# snc98_main_cpu.net
KiCad netlist of a schematic drawn in EAGLE
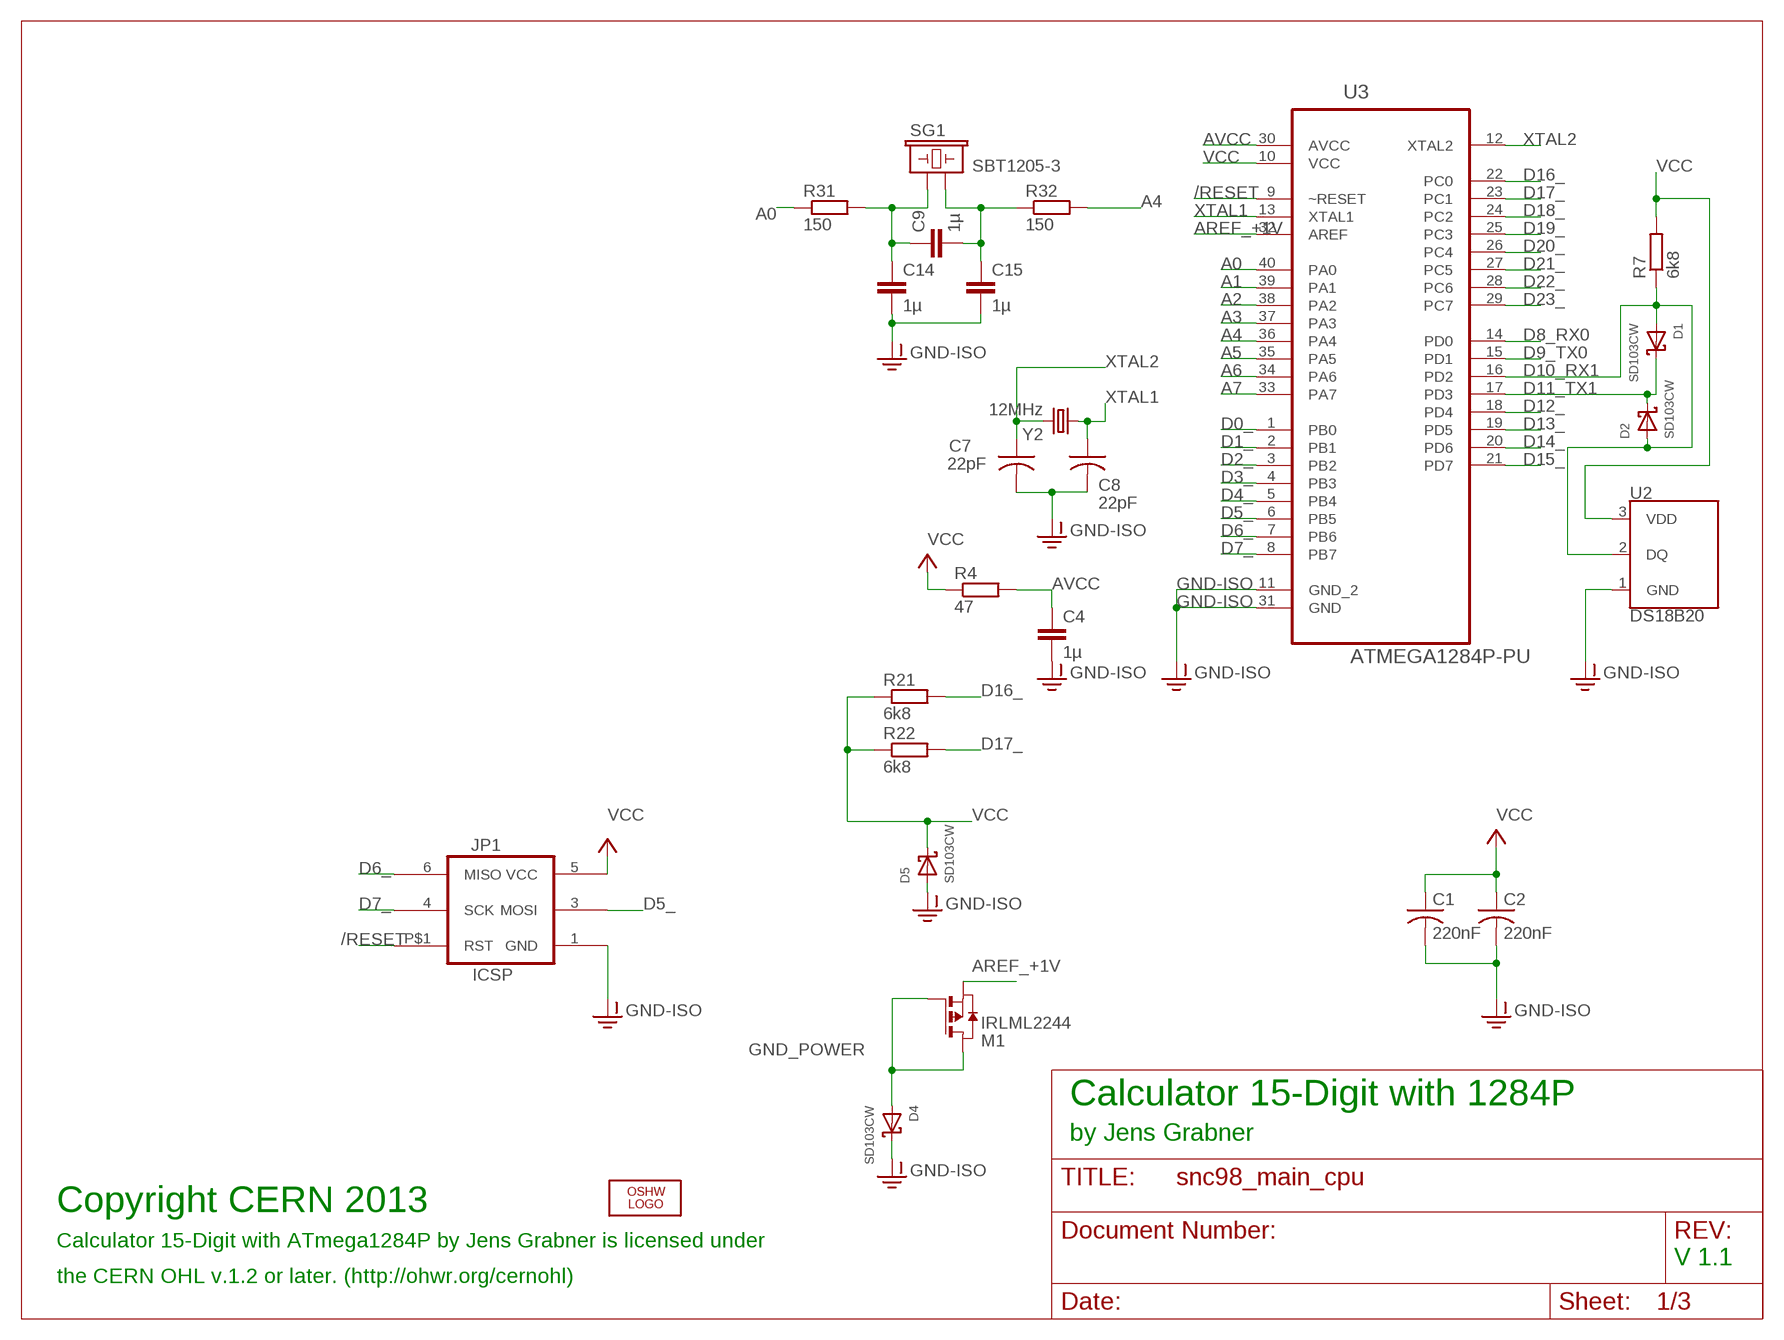
[diagram p0: schematic, sheet 1]
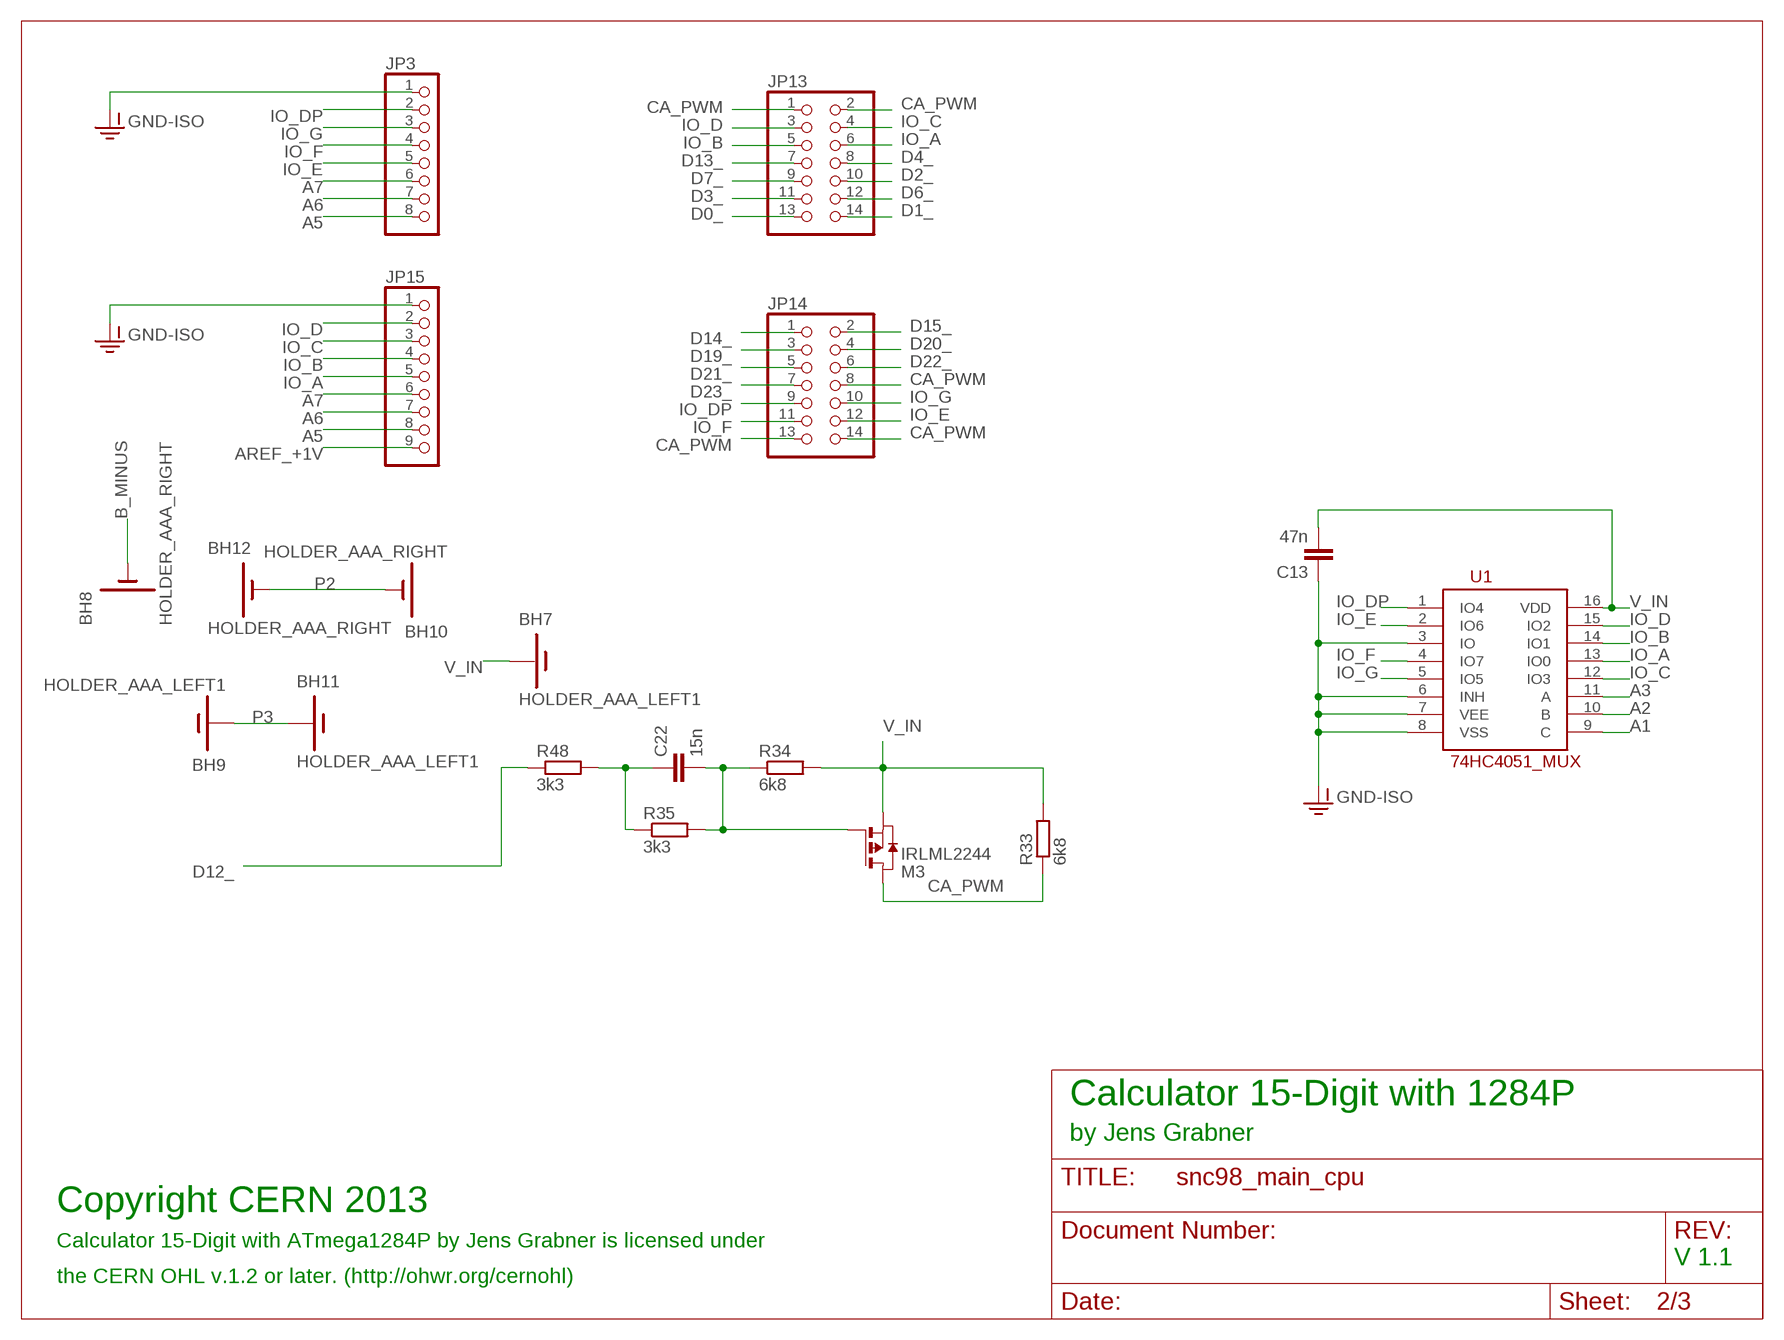
[diagram p1: schematic, sheet 2]
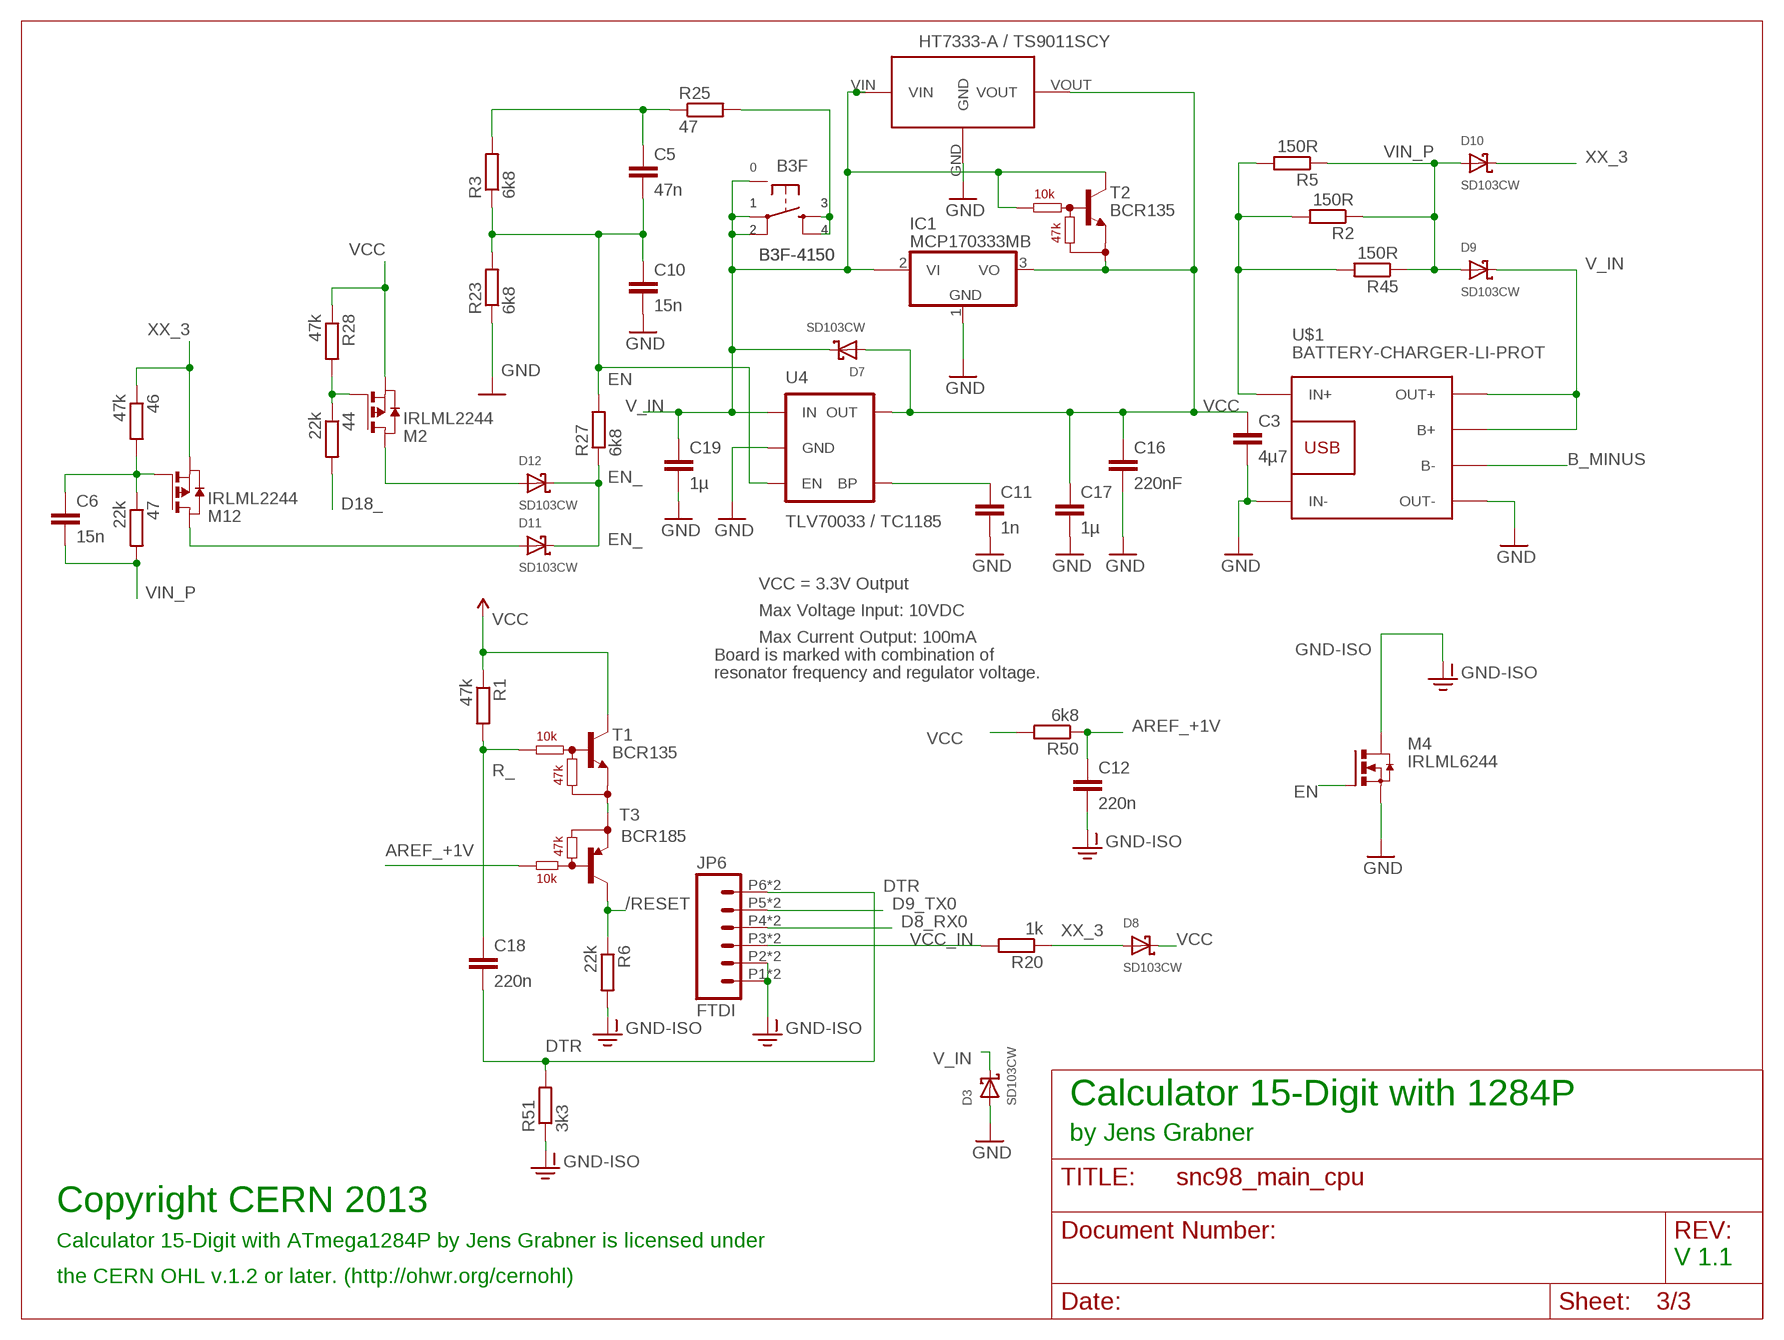
[diagram p2: schematic, sheet 3]

(export (version "E")
  (design (tool "Eeschema 10.0.6"))
  (components
    (comp (ref "BH7")
      (value "HOLDER_AAA_LEFT1")
      (footprint "eagle-import:BATTERY-AAA-LEFT")
      (libsource (lib "eagle-import") (part "HOLDER_AAA_LEFT1"))
    )
    (comp (ref "BH8")
      (value "HOLDER_AAA_RIGHT")
      (footprint "eagle-import:BATTERY-AAA-RIGHT")
      (libsource (lib "eagle-import") (part "HOLDER_AAA_RIGHT"))
    )
    (comp (ref "BH9")
      (value "HOLDER_AAA_LEFT1")
      (footprint "eagle-import:BATTERY-AAA-LEFT")
      (fields (field (name "TME_EU") "BC-0401"))
      (libsource (lib "eagle-import") (part "HOLDER_AAA_LEFT1"))
    )
    (comp (ref "BH10")
      (value "HOLDER_AAA_RIGHT")
      (footprint "eagle-import:BATTERY-AAA-RIGHT")
      (libsource (lib "eagle-import") (part "HOLDER_AAA_RIGHT"))
    )
    (comp (ref "BH11")
      (value "HOLDER_AAA_LEFT1")
      (footprint "eagle-import:BATTERY-AAA-LEFT")
      (libsource (lib "eagle-import") (part "HOLDER_AAA_LEFT1"))
    )
    (comp (ref "BH12")
      (value "HOLDER_AAA_RIGHT")
      (footprint "eagle-import:BATTERY-AAA-RIGHT")
      (libsource (lib "eagle-import") (part "HOLDER_AAA_RIGHT"))
    )
    (comp (ref "C13")
      (value "47n")
      (footprint "eagle-import:C1206K")
      (fields (field (name "TME_EU") "CC0805KRX7R9473"))
      (libsource (lib "eagle-import") (part "C-EUC1206K"))
    )
    (comp (ref "C22")
      (value "15n")
      (footprint "eagle-import:C1206K")
      (fields (field (name "TME_EU") "CC0805KRX7R9153"))
      (libsource (lib "eagle-import") (part "C-EUC1206K"))
    )
    (comp (ref "JP3")
      (value "PINHD-1X8CLEANBIG")
      (footprint "eagle-import:1X08-CLEANBIG")
      (libsource (lib "eagle-import") (part "PINHD-1X8CLEANBIG"))
    )
    (comp (ref "JP13")
      (value "PINHD-2X7")
      (footprint "eagle-import:2X07")
      (libsource (lib "eagle-import") (part "PINHD-2X7"))
    )
    (comp (ref "JP14")
      (value "PINHD-2X7")
      (footprint "eagle-import:2X07")
      (libsource (lib "eagle-import") (part "PINHD-2X7"))
    )
    (comp (ref "JP15")
      (value "PINHD-1X9")
      (footprint "eagle-import:1X09-BIG")
      (libsource (lib "eagle-import") (part "PINHD-1X9"))
    )
    (comp (ref "M3")
      (value "IRLML2244")
      (footprint "eagle-import:SOT-23")
      (fields (field (name "MF") "INFINEON") (field (name "MPN") "IRLML2244TRPBF"))
      (libsource (lib "eagle-import") (part "IRLML6402"))
    )
    (comp (ref "R33")
      (value "6k8")
      (footprint "eagle-import:R1206")
      (libsource (lib "eagle-import") (part "R-EU_R1206"))
    )
    (comp (ref "R34")
      (value "6k8")
      (footprint "eagle-import:R1206")
      (libsource (lib "eagle-import") (part "R-EU_R1206"))
    )
    (comp (ref "R35")
      (value "3k3")
      (footprint "eagle-import:R1206")
      (libsource (lib "eagle-import") (part "R-EU_R1206"))
    )
    (comp (ref "R48")
      (value "3k3")
      (footprint "eagle-import:R1206")
      (libsource (lib "eagle-import") (part "R-EU_R1206"))
    )
    (comp (ref "U1")
      (value "74HC4051_MUX")
      (footprint "eagle-import:SO16")
      (libsource (lib "eagle-import") (part "74HC4051_MUX"))
    )
    (comp (ref "44")
      (value "22k")
      (footprint "eagle-import:R1206")
      (libsource (lib "eagle-import") (part "R-EU_R1206"))
    )
    (comp (ref "46")
      (value "47k")
      (footprint "eagle-import:R1206")
      (libsource (lib "eagle-import") (part "R-EU_R1206"))
    )
    (comp (ref "47")
      (value "22k")
      (footprint "eagle-import:R1206")
      (libsource (lib "eagle-import") (part "R-EU_R1206"))
    )
    (comp (ref "C3")
      (value "4µ7")
      (footprint "eagle-import:C1206K")
      (libsource (lib "eagle-import") (part "C-EUC1206K"))
    )
    (comp (ref "C5")
      (value "47n")
      (footprint "eagle-import:C1206K")
      (fields (field (name "TME_EU") "CC0805KRX7R9473"))
      (libsource (lib "eagle-import") (part "C-EUC1206K"))
    )
    (comp (ref "C6")
      (value "15n")
      (footprint "eagle-import:C1206K")
      (fields (field (name "TME_EU") "CC0805KRX7R9153"))
      (libsource (lib "eagle-import") (part "C-EUC1206K"))
    )
    (comp (ref "C10")
      (value "15n")
      (footprint "eagle-import:C1206K")
      (fields (field (name "TME_EU") "CC0805KRX7R9153"))
      (libsource (lib "eagle-import") (part "C-EUC1206K"))
    )
    (comp (ref "C11")
      (value "1n")
      (footprint "eagle-import:0805")
      (libsource (lib "eagle-import") (part "CAP0805"))
    )
    (comp (ref "C12")
      (value "220n")
      (footprint "eagle-import:0805")
      (libsource (lib "eagle-import") (part "CAP0805"))
    )
    (comp (ref "C16")
      (value "220nF")
      (footprint "eagle-import:0805")
      (libsource (lib "eagle-import") (part "CAP0805"))
    )
    (comp (ref "C17")
      (value "1µ")
      (footprint "eagle-import:C1206K")
      (libsource (lib "eagle-import") (part "C-EUC1206K"))
    )
    (comp (ref "C18")
      (value "220n")
      (footprint "eagle-import:C1206K")
      (fields (field (name "TME_EU") "CC0805KPX7R7224"))
      (libsource (lib "eagle-import") (part "C-EUC1206K"))
    )
    (comp (ref "C19")
      (value "1µ")
      (footprint "eagle-import:C1206K")
      (libsource (lib "eagle-import") (part "C-EUC1206K"))
    )
    (comp (ref "D3")
      (value "SD103CW")
      (footprint "eagle-import:SOD-123F")
      (fields (field (name "MF") "MULTICOMP") (field (name "MPN") "SD103CW-7-F"))
      (libsource (lib "eagle-import") (part "DIODESOD-123F"))
    )
    (comp (ref "D7")
      (value "SD103CW")
      (footprint "eagle-import:SOD-123F")
      (fields (field (name "MF") "MULTICOMP") (field (name "MPN") "SD103CW-7-F"))
      (libsource (lib "eagle-import") (part "DIODESOD-123F"))
    )
    (comp (ref "D8")
      (value "SD103CW")
      (footprint "eagle-import:SOD-123F")
      (fields (field (name "MF") "MULTICOMP") (field (name "MPN") "SD103CW-7-F"))
      (libsource (lib "eagle-import") (part "DIODESOD-123F"))
    )
    (comp (ref "D9")
      (value "SD103CW")
      (footprint "eagle-import:SOD-123F")
      (fields (field (name "MF") "MULTICOMP") (field (name "MPN") "SD103CW-7-F"))
      (libsource (lib "eagle-import") (part "DIODESOD-123F"))
    )
    (comp (ref "D10")
      (value "SD103CW")
      (footprint "eagle-import:SOD-123F")
      (fields (field (name "MF") "MULTICOMP") (field (name "MPN") "SD103CW-7-F"))
      (libsource (lib "eagle-import") (part "DIODESOD-123F"))
    )
    (comp (ref "D11")
      (value "SD103CW")
      (footprint "eagle-import:SOD-123F")
      (fields (field (name "MF") "MULTICOMP") (field (name "MPN") "SD103CW-7-F"))
      (libsource (lib "eagle-import") (part "DIODESOD-123F"))
    )
    (comp (ref "D12")
      (value "SD103CW")
      (footprint "eagle-import:SOD-123F")
      (fields (field (name "MF") "MULTICOMP") (field (name "MPN") "SD103CW-7-F"))
      (libsource (lib "eagle-import") (part "DIODESOD-123F"))
    )
    (comp (ref "IC1")
      (value "MCP170333MB")
      (footprint "eagle-import:SOT89")
      (libsource (lib "eagle-import") (part "MCP1703MB33"))
    )
    (comp (ref "JP6")
      (value "FTDI")
      (footprint "eagle-import:1X06_LOCK")
      (libsource (lib "eagle-import") (part "M06LOCK"))
    )
    (comp (ref "M2")
      (value "IRLML2244")
      (footprint "eagle-import:SOT-23")
      (fields (field (name "MF") "INFINEON") (field (name "MPN") "IRLML2244TRPBF"))
      (libsource (lib "eagle-import") (part "IRLML6402"))
    )
    (comp (ref "M4")
      (value "IRLML6244")
      (footprint "eagle-import:SOT-23")
      (fields (field (name "MF") "INFINEON") (field (name "MPN") "IRLML6244TRPBF"))
      (libsource (lib "eagle-import") (part "IRLML2502M"))
    )
    (comp (ref "M12")
      (value "IRLML2244")
      (footprint "eagle-import:SOT-23")
      (fields (field (name "MF") "INFINEON") (field (name "MPN") "IRLML2244TRPBF"))
      (libsource (lib "eagle-import") (part "IRLML6402"))
    )
    (comp (ref "R1")
      (value "47k")
      (footprint "eagle-import:R1206")
      (libsource (lib "eagle-import") (part "R-EU_R1206"))
    )
    (comp (ref "R2")
      (value "150R")
      (footprint "eagle-import:0204_5")
      (libsource (lib "eagle-import") (part "R-EU_0204/5"))
    )
    (comp (ref "R3")
      (value "6k8")
      (footprint "eagle-import:R1206")
      (libsource (lib "eagle-import") (part "R-EU_R1206"))
    )
    (comp (ref "R5")
      (value "150R")
      (footprint "eagle-import:0207_10")
      (libsource (lib "eagle-import") (part "R-EU_0207/10"))
    )
    (comp (ref "R6")
      (value "22k")
      (footprint "eagle-import:R1206")
      (libsource (lib "eagle-import") (part "R-EU_R1206"))
    )
    (comp (ref "R20")
      (value "1k")
      (footprint "eagle-import:R1206")
      (libsource (lib "eagle-import") (part "R-EU_R1206"))
    )
    (comp (ref "R23")
      (value "6k8")
      (footprint "eagle-import:R1206")
      (libsource (lib "eagle-import") (part "R-EU_R1206"))
    )
    (comp (ref "R25")
      (value "47")
      (footprint "eagle-import:R1206")
      (libsource (lib "eagle-import") (part "R-EU_R1206"))
    )
    (comp (ref "R27")
      (value "6k8")
      (footprint "eagle-import:R1206")
      (libsource (lib "eagle-import") (part "R-EU_R1206"))
    )
    (comp (ref "R28")
      (value "47k")
      (footprint "eagle-import:R1206")
      (libsource (lib "eagle-import") (part "R-EU_R1206"))
    )
    (comp (ref "R45")
      (value "150R")
      (footprint "eagle-import:R1206")
      (libsource (lib "eagle-import") (part "R-EU_R1206"))
    )
    (comp (ref "R50")
      (value "6k8")
      (footprint "eagle-import:R1206")
      (libsource (lib "eagle-import") (part "R-EU_R1206"))
    )
    (comp (ref "R51")
      (value "3k3")
      (footprint "eagle-import:R1206")
      (libsource (lib "eagle-import") (part "R-EU_R1206"))
    )
    (comp (ref "S3")
      (value "B3F-4150")
      (footprint "eagle-import:TACTILE-PTH-12MM")
      (fields (field (name "MF") "OMRON") (field (name "MPN") "B3F4150"))
      (libsource (lib "eagle-import") (part "TACTILE_SWITCHTACTILE_SWITCH_PTH-12MM"))
    )
    (comp (ref "T1")
      (value "BCR135")
      (footprint "eagle-import:SOT23-BEC")
      (fields (field (name "MF") "INFINEON") (field (name "MPN") "BCR135E6327HTSA1"))
      (libsource (lib "eagle-import") (part "BCR135"))
    )
    (comp (ref "T2")
      (value "BCR135")
      (footprint "eagle-import:SOT23-BEC")
      (fields (field (name "MF") "INFINEON") (field (name "MPN") "BCR135E6327HTSA1"))
      (libsource (lib "eagle-import") (part "BCR135"))
    )
    (comp (ref "T3")
      (value "BCR185")
      (footprint "eagle-import:SOT23-R_INFINEON")
      (fields (field (name "MF") "ROHM") (field (name "MPN") "DTA114YKAT146"))
      (libsource (lib "eagle-import") (part "BCR185"))
    )
    (comp (ref "U$1")
      (value "BATTERY-CHARGER-LI-PROT")
      (footprint "eagle-import:BATTERY-CHARGER-LI-PROT")
      (libsource (lib "eagle-import") (part "BATTERY-CHARGER-LI-PROT"))
    )
    (comp (ref "U$3")
      (value "HT7333 / TS9011SCY")
      (footprint "eagle-import:SOT89")
      (libsource (lib "eagle-import") (part "HT7333"))
    )
    (comp (ref "U4")
      (value "TLV70033 / TC1185")
      (footprint "eagle-import:SOT23-5")
      (libsource (lib "eagle-import") (part "V_REG_LDOSMD"))
    )
    (comp (ref "C1")
      (value "220nF")
      (footprint "eagle-import:C1206K")
      (libsource (lib "eagle-import") (part "C-USC1206K"))
    )
    (comp (ref "C2")
      (value "220nF")
      (footprint "eagle-import:C1206K")
      (libsource (lib "eagle-import") (part "C-USC1206K"))
    )
    (comp (ref "C4")
      (value "1µ")
      (footprint "eagle-import:C1206K")
      (libsource (lib "eagle-import") (part "C-EUC1206K"))
    )
    (comp (ref "C7")
      (value "22pF")
      (footprint "eagle-import:C0805K")
      (libsource (lib "eagle-import") (part "C-USC0805K"))
    )
    (comp (ref "C8")
      (value "22pF")
      (footprint "eagle-import:C0805K")
      (libsource (lib "eagle-import") (part "C-USC0805K"))
    )
    (comp (ref "C9")
      (value "1µ")
      (footprint "eagle-import:C1206K")
      (libsource (lib "eagle-import") (part "C-EUC1206K"))
    )
    (comp (ref "C14")
      (value "1µ")
      (footprint "eagle-import:C1206K")
      (libsource (lib "eagle-import") (part "C-EUC1206K"))
    )
    (comp (ref "C15")
      (value "1µ")
      (footprint "eagle-import:C1206K")
      (libsource (lib "eagle-import") (part "C-EUC1206K"))
    )
    (comp (ref "D1")
      (value "SD103CW")
      (footprint "eagle-import:SOD-323")
      (fields (field (name "MF") "MULTICOMP") (field (name "MPN") "SD103CW-7-F"))
      (libsource (lib "eagle-import") (part "DIODESOD-323"))
    )
    (comp (ref "D2")
      (value "SD103CW")
      (footprint "eagle-import:SOD-123")
      (fields (field (name "MF") "MULTICOMP") (field (name "MPN") "SD103CW-7-F"))
      (libsource (lib "eagle-import") (part "DIODESOD-123"))
    )
    (comp (ref "D4")
      (value "SD103CW")
      (footprint "eagle-import:SOD-123F")
      (fields (field (name "MF") "MULTICOMP") (field (name "MPN") "SD103CW-7-F"))
      (libsource (lib "eagle-import") (part "DIODESOD-123F"))
    )
    (comp (ref "D5")
      (value "SD103CW")
      (footprint "eagle-import:SOD-123F")
      (fields (field (name "MF") "MULTICOMP") (field (name "MPN") "SD103CW-7-F"))
      (libsource (lib "eagle-import") (part "DIODESOD-123F"))
    )
    (comp (ref "JP1")
      (value "ICSP")
      (footprint "eagle-import:2X3_SMD_VERTICAL")
      (libsource (lib "eagle-import") (part "AVR_SPI_PRG_6"))
    )
    (comp (ref "LOGO1")
      (value "OSHW_LOGO_8MILX0150-NT")
      (footprint "eagle-import:OSHW_8X150_NOTEXT")
      (libsource (lib "eagle-import") (part "OSHW_LOGO_8MILX0150-NT"))
    )
    (comp (ref "M1")
      (value "IRLML2244")
      (footprint "eagle-import:SOT-23")
      (fields
        (field (name "MF") "INFINEON")
        (field (name "MPN") "IRLML2244TRPBF")
        (field (name "TME_EU") "DMG2305UX-7")
      )
      (libsource (lib "eagle-import") (part "IRLML6402"))
    )
    (comp (ref "R4")
      (value "47")
      (footprint "eagle-import:R1206")
      (libsource (lib "eagle-import") (part "R-EU_R1206"))
    )
    (comp (ref "R7")
      (value "6k8")
      (footprint "eagle-import:R1206")
      (libsource (lib "eagle-import") (part "R-EU_R1206"))
    )
    (comp (ref "R21")
      (value "6k8")
      (footprint "eagle-import:R1206")
      (libsource (lib "eagle-import") (part "R-EU_R1206"))
    )
    (comp (ref "R22")
      (value "6k8")
      (footprint "eagle-import:R1206")
      (libsource (lib "eagle-import") (part "R-EU_R1206"))
    )
    (comp (ref "R31")
      (value "150")
      (footprint "eagle-import:R1206")
      (libsource (lib "eagle-import") (part "R-EU_R1206"))
    )
    (comp (ref "R32")
      (value "150")
      (footprint "eagle-import:R1206")
      (libsource (lib "eagle-import") (part "R-EU_R1206"))
    )
    (comp (ref "SG1")
      (value "SBT1205-3")
      (footprint "eagle-import:BUZZER-12MM-NS")
      (libsource (lib "eagle-import") (part "BUZZERNS"))
    )
    (comp (ref "U2")
      (value "DS18B20")
      (footprint "eagle-import:TO-92-AMMO")
      (libsource (lib "eagle-import") (part "DS18B20"))
    )
    (comp (ref "U3")
      (value "ATMEGA1284P-PU")
      (footprint "eagle-import:DIP254P1524X483-40")
      (fields (field (name "MF") "MICROCHIP"))
      (libsource (lib "eagle-import") (part "ATMEGA1284P-PU"))
    )
    (comp (ref "Y2")
      (value "12MHz")
      (footprint "eagle-import:HC49U-V")
      (libsource (lib "eagle-import") (part "CRYSTALHC49UV"))
    )
  )
  (nets
    (net (code "1") (name "A0") (class "Default")
      (node (ref "R31") (pin "1") (pinfunction "1_1") (pintype "passive"))
      (node (ref "U3") (pin "40") (pinfunction "PA0_40") (pintype "bidirectional"))
    )
    (net (code "2") (name "A1") (class "Default")
      (node (ref "U1") (pin "9") (pinfunction "C_9") (pintype "bidirectional"))
      (node (ref "U3") (pin "39") (pinfunction "PA1_39") (pintype "bidirectional"))
    )
    (net (code "3") (name "A2") (class "Default")
      (node (ref "U1") (pin "10") (pinfunction "B_10") (pintype "bidirectional"))
      (node (ref "U3") (pin "38") (pinfunction "PA2_38") (pintype "bidirectional"))
    )
    (net (code "4") (name "A3") (class "Default")
      (node (ref "U1") (pin "11") (pinfunction "A_11") (pintype "bidirectional"))
      (node (ref "U3") (pin "37") (pinfunction "PA3_37") (pintype "bidirectional"))
    )
    (net (code "5") (name "A4") (class "Default")
      (node (ref "R32") (pin "2") (pinfunction "2_2") (pintype "passive"))
      (node (ref "U3") (pin "36") (pinfunction "PA4_36") (pintype "bidirectional"))
    )
    (net (code "6") (name "A5") (class "Default")
      (node (ref "JP15") (pin "8") (pinfunction "8_8") (pintype "passive"))
      (node (ref "JP3") (pin "8") (pinfunction "8_8") (pintype "passive"))
      (node (ref "U3") (pin "35") (pinfunction "PA5_35") (pintype "bidirectional"))
    )
    (net (code "7") (name "A6") (class "Default")
      (node (ref "JP15") (pin "7") (pinfunction "7_7") (pintype "passive"))
      (node (ref "JP3") (pin "7") (pinfunction "7_7") (pintype "passive"))
      (node (ref "U3") (pin "34") (pinfunction "PA6_34") (pintype "bidirectional"))
    )
    (net (code "8") (name "A7") (class "Default")
      (node (ref "JP15") (pin "6") (pinfunction "6_6") (pintype "passive"))
      (node (ref "JP3") (pin "6") (pinfunction "6_6") (pintype "passive"))
      (node (ref "U3") (pin "33") (pinfunction "PA7_33") (pintype "bidirectional"))
    )
    (net (code "9") (name "AREF_+1V") (class "Default")
      (node (ref "C12") (pin "3") (pinfunction "1_3") (pintype "passive"))
      (node (ref "JP15") (pin "9") (pinfunction "9_9") (pintype "passive"))
      (node (ref "M1") (pin "2") (pinfunction "S_2") (pintype "passive"))
      (node (ref "R50") (pin "1") (pinfunction "1_1") (pintype "passive"))
      (node (ref "T3") (pin "B") (pinfunction "B_B") (pintype "passive"))
      (node (ref "U3") (pin "32") (pinfunction "AREF_32") (pintype "input"))
    )
    (net (code "10") (name "AVCC") (class "Default")
      (node (ref "C4") (pin "1") (pinfunction "1_1") (pintype "passive"))
      (node (ref "R4") (pin "2") (pinfunction "2_2") (pintype "passive"))
      (node (ref "U3") (pin "30") (pinfunction "AVCC_30") (pintype "power_in"))
    )
    (net (code "11") (name "B_MINUS") (class "Default")
      (node (ref "BH8") (pin "M1") (pinfunction "-_M1") (pintype "power_in"))
      (node (ref "BH8") (pin "M2") (pinfunction "-_M2") (pintype "power_in"))
      (node (ref "BH8") (pin "M3") (pinfunction "-_M3") (pintype "power_in"))
      (node (ref "BH8") (pin "M4") (pinfunction "-_M4") (pintype "power_in"))
      (node (ref "U$1") (pin "B-") (pinfunction "B-_B-") (pintype "bidirectional"))
    )
    (net (code "12") (name "CA_PWM") (class "Default")
      (node (ref "JP13") (pin "1") (pinfunction "1_1") (pintype "passive"))
      (node (ref "JP13") (pin "2") (pinfunction "2_2") (pintype "passive"))
      (node (ref "JP14") (pin "13") (pinfunction "13_13") (pintype "passive"))
      (node (ref "JP14") (pin "14") (pinfunction "14_14") (pintype "passive"))
      (node (ref "JP14") (pin "8") (pinfunction "8_8") (pintype "passive"))
      (node (ref "M3") (pin "3") (pinfunction "D_3") (pintype "passive"))
      (node (ref "R33") (pin "1") (pinfunction "1_1") (pintype "passive"))
    )
    (net (code "13") (name "D0_") (class "Default")
      (node (ref "JP13") (pin "13") (pinfunction "13_13") (pintype "passive"))
      (node (ref "U3") (pin "1") (pinfunction "PB0_1") (pintype "bidirectional"))
    )
    (net (code "14") (name "D1_") (class "Default")
      (node (ref "JP13") (pin "14") (pinfunction "14_14") (pintype "passive"))
      (node (ref "U3") (pin "2") (pinfunction "PB1_2") (pintype "bidirectional"))
    )
    (net (code "15") (name "D2_") (class "Default")
      (node (ref "JP13") (pin "10") (pinfunction "10_10") (pintype "passive"))
      (node (ref "U3") (pin "3") (pinfunction "PB2_3") (pintype "bidirectional"))
    )
    (net (code "16") (name "D3_") (class "Default")
      (node (ref "JP13") (pin "11") (pinfunction "11_11") (pintype "passive"))
      (node (ref "U3") (pin "4") (pinfunction "PB3_4") (pintype "bidirectional"))
    )
    (net (code "17") (name "D4_") (class "Default")
      (node (ref "JP13") (pin "8") (pinfunction "8_8") (pintype "passive"))
      (node (ref "U3") (pin "5") (pinfunction "PB4_5") (pintype "bidirectional"))
    )
    (net (code "18") (name "D5_") (class "Default")
      (node (ref "JP1") (pin "3") (pinfunction "MOSI_3") (pintype "passive"))
      (node (ref "U3") (pin "6") (pinfunction "PB5_6") (pintype "bidirectional"))
    )
    (net (code "19") (name "D6_") (class "Default")
      (node (ref "JP1") (pin "6") (pinfunction "MISO_6") (pintype "passive"))
      (node (ref "JP13") (pin "12") (pinfunction "12_12") (pintype "passive"))
      (node (ref "U3") (pin "7") (pinfunction "PB6_7") (pintype "bidirectional"))
    )
    (net (code "20") (name "D7_") (class "Default")
      (node (ref "JP1") (pin "4") (pinfunction "SCK_4") (pintype "passive"))
      (node (ref "JP13") (pin "9") (pinfunction "9_9") (pintype "passive"))
      (node (ref "U3") (pin "8") (pinfunction "PB7_8") (pintype "bidirectional"))
    )
    (net (code "21") (name "D8_RX0") (class "Default")
      (node (ref "JP6") (pin "P4") (pinfunction "4_P4") (pintype "passive"))
      (node (ref "JP6") (pin "P4A") (pinfunction "4_P4A") (pintype "passive"))
      (node (ref "U3") (pin "14") (pinfunction "PD0_14") (pintype "bidirectional"))
    )
    (net (code "22") (name "D9_TX0") (class "Default")
      (node (ref "JP6") (pin "P5") (pinfunction "5_P5") (pintype "passive"))
      (node (ref "JP6") (pin "P5A") (pinfunction "5_P5A") (pintype "passive"))
      (node (ref "U3") (pin "15") (pinfunction "PD1_15") (pintype "bidirectional"))
    )
    (net (code "23") (name "D10_RX1") (class "Default")
      (node (ref "D1") (pin "A") (pinfunction "A_A") (pintype "passive"))
      (node (ref "D2") (pin "A") (pinfunction "A_A") (pintype "passive"))
      (node (ref "R7") (pin "1") (pinfunction "1_1") (pintype "passive"))
      (node (ref "U2") (pin "2") (pinfunction "DQ_2") (pintype "bidirectional"))
      (node (ref "U3") (pin "16") (pinfunction "PD2_16") (pintype "bidirectional"))
    )
    (net (code "24") (name "D11_TX1") (class "Default")
      (node (ref "D1") (pin "C") (pinfunction "C_C") (pintype "passive"))
      (node (ref "D2") (pin "C") (pinfunction "C_C") (pintype "passive"))
      (node (ref "U3") (pin "17") (pinfunction "PD3_17") (pintype "bidirectional"))
    )
    (net (code "25") (name "D12_") (class "Default")
      (node (ref "R48") (pin "1") (pinfunction "1_1") (pintype "passive"))
      (node (ref "U3") (pin "18") (pinfunction "PD4_18") (pintype "bidirectional"))
    )
    (net (code "26") (name "D13_") (class "Default")
      (node (ref "JP13") (pin "7") (pinfunction "7_7") (pintype "passive"))
      (node (ref "U3") (pin "19") (pinfunction "PD5_19") (pintype "bidirectional"))
    )
    (net (code "27") (name "D14_") (class "Default")
      (node (ref "JP14") (pin "1") (pinfunction "1_1") (pintype "passive"))
      (node (ref "U3") (pin "20") (pinfunction "PD6_20") (pintype "bidirectional"))
    )
    (net (code "28") (name "D15_") (class "Default")
      (node (ref "JP14") (pin "2") (pinfunction "2_2") (pintype "passive"))
      (node (ref "U3") (pin "21") (pinfunction "PD7_21") (pintype "bidirectional"))
    )
    (net (code "29") (name "D16_") (class "Default")
      (node (ref "R21") (pin "2") (pinfunction "2_2") (pintype "passive"))
      (node (ref "U3") (pin "22") (pinfunction "PC0_22") (pintype "bidirectional"))
    )
    (net (code "30") (name "D17_") (class "Default")
      (node (ref "R22") (pin "2") (pinfunction "2_2") (pintype "passive"))
      (node (ref "U3") (pin "23") (pinfunction "PC1_23") (pintype "bidirectional"))
    )
    (net (code "31") (name "D18_") (class "Default")
      (node (ref "44") (pin "2") (pinfunction "2_2") (pintype "passive"))
      (node (ref "U3") (pin "24") (pinfunction "PC2_24") (pintype "bidirectional"))
    )
    (net (code "32") (name "D19_") (class "Default")
      (node (ref "JP14") (pin "3") (pinfunction "3_3") (pintype "passive"))
      (node (ref "U3") (pin "25") (pinfunction "PC3_25") (pintype "bidirectional"))
    )
    (net (code "33") (name "D20_") (class "Default")
      (node (ref "JP14") (pin "4") (pinfunction "4_4") (pintype "passive"))
      (node (ref "U3") (pin "26") (pinfunction "PC4_26") (pintype "bidirectional"))
    )
    (net (code "34") (name "D21_") (class "Default")
      (node (ref "JP14") (pin "5") (pinfunction "5_5") (pintype "passive"))
      (node (ref "U3") (pin "27") (pinfunction "PC5_27") (pintype "bidirectional"))
    )
    (net (code "35") (name "D22_") (class "Default")
      (node (ref "JP14") (pin "6") (pinfunction "6_6") (pintype "passive"))
      (node (ref "U3") (pin "28") (pinfunction "PC6_28") (pintype "bidirectional"))
    )
    (net (code "36") (name "D23_") (class "Default")
      (node (ref "JP14") (pin "7") (pinfunction "7_7") (pintype "passive"))
      (node (ref "U3") (pin "29") (pinfunction "PC7_29") (pintype "bidirectional"))
    )
    (net (code "37") (name "DTR") (class "Default")
      (node (ref "C18") (pin "2") (pinfunction "2_2") (pintype "passive"))
      (node (ref "JP6") (pin "P6") (pinfunction "6_P6") (pintype "passive"))
      (node (ref "JP6") (pin "P6A") (pinfunction "6_P6A") (pintype "passive"))
      (node (ref "R51") (pin "2") (pinfunction "2_2") (pintype "passive"))
    )
    (net (code "38") (name "EN") (class "Default")
      (node (ref "C10") (pin "1") (pinfunction "1_1") (pintype "passive"))
      (node (ref "C5") (pin "2") (pinfunction "2_2") (pintype "passive"))
      (node (ref "M4") (pin "1") (pinfunction "G_1") (pintype "passive"))
      (node (ref "R23") (pin "2") (pinfunction "2_2") (pintype "passive"))
      (node (ref "R27") (pin "2") (pinfunction "2_2") (pintype "passive"))
      (node (ref "R3") (pin "1") (pinfunction "1_1") (pintype "passive"))
      (node (ref "U4") (pin "3") (pinfunction "EN_3") (pintype "input"))
    )
    (net (code "39") (name "EN_") (class "Default")
      (node (ref "D11") (pin "C") (pinfunction "C_C") (pintype "passive"))
      (node (ref "D12") (pin "C") (pinfunction "C_C") (pintype "passive"))
      (node (ref "R27") (pin "1") (pinfunction "1_1") (pintype "passive"))
    )
    (net (code "40") (name "GND") (class "Default")
      (node (ref "C10") (pin "2") (pinfunction "2_2") (pintype "passive"))
      (node (ref "C11") (pin "4") (pinfunction "2_4") (pintype "passive"))
      (node (ref "C16") (pin "4") (pinfunction "2_4") (pintype "passive"))
      (node (ref "C17") (pin "2") (pinfunction "2_2") (pintype "passive"))
      (node (ref "C19") (pin "2") (pinfunction "2_2") (pintype "passive"))
      (node (ref "C3") (pin "2") (pinfunction "2_2") (pintype "passive"))
      (node (ref "D3") (pin "A") (pinfunction "A_A") (pintype "passive"))
      (node (ref "IC1") (pin "1") (pinfunction "GND_1") (pintype "passive"))
      (node (ref "M4") (pin "2") (pinfunction "S_2") (pintype "passive"))
      (node (ref "R23") (pin "1") (pinfunction "1_1") (pintype "passive"))
      (node (ref "U$1") (pin "IN-") (pinfunction "IN-_IN-") (pintype "bidirectional"))
      (node (ref "U$1") (pin "OUT-") (pinfunction "OUT-_OUT-") (pintype "bidirectional"))
      (node (ref "U$3") (pin "GND") (pinfunction "GND_GND") (pintype "bidirectional"))
      (node (ref "U4") (pin "2") (pinfunction "GND_2") (pintype "input"))
    )
    (net (code "41") (name "GND-ISO") (class "Default")
      (node (ref "C1") (pin "2") (pinfunction "2_2") (pintype "passive"))
      (node (ref "C12") (pin "4") (pinfunction "2_4") (pintype "passive"))
      (node (ref "C13") (pin "1") (pinfunction "1_1") (pintype "passive"))
      (node (ref "C14") (pin "2") (pinfunction "2_2") (pintype "passive"))
      (node (ref "C15") (pin "2") (pinfunction "2_2") (pintype "passive"))
      (node (ref "C2") (pin "2") (pinfunction "2_2") (pintype "passive"))
      (node (ref "C4") (pin "2") (pinfunction "2_2") (pintype "passive"))
      (node (ref "C7") (pin "2") (pinfunction "2_2") (pintype "passive"))
      (node (ref "C8") (pin "2") (pinfunction "2_2") (pintype "passive"))
      (node (ref "D4") (pin "C") (pinfunction "C_C") (pintype "passive"))
      (node (ref "D5") (pin "A") (pinfunction "A_A") (pintype "passive"))
      (node (ref "JP1") (pin "1") (pinfunction "GND_1") (pintype "passive"))
      (node (ref "JP15") (pin "1") (pinfunction "1_1") (pintype "passive"))
      (node (ref "JP3") (pin "1") (pinfunction "1_1") (pintype "passive"))
      (node (ref "JP6") (pin "P1") (pinfunction "1_P1") (pintype "passive"))
      (node (ref "JP6") (pin "P1A") (pinfunction "1_P1A") (pintype "passive"))
      (node (ref "JP6") (pin "P2") (pinfunction "2_P2") (pintype "passive"))
      (node (ref "JP6") (pin "P2A") (pinfunction "2_P2A") (pintype "passive"))
      (node (ref "M4") (pin "3") (pinfunction "D_3") (pintype "passive"))
      (node (ref "R51") (pin "1") (pinfunction "1_1") (pintype "passive"))
      (node (ref "R6") (pin "2") (pinfunction "2_2") (pintype "passive"))
      (node (ref "U1") (pin "3") (pinfunction "IO_3") (pintype "bidirectional"))
      (node (ref "U1") (pin "6") (pinfunction "INH_6") (pintype "bidirectional"))
      (node (ref "U1") (pin "7") (pinfunction "VEE_7") (pintype "bidirectional"))
      (node (ref "U1") (pin "8") (pinfunction "VSS_8") (pintype "bidirectional"))
      (node (ref "U2") (pin "1") (pinfunction "GND_1") (pintype "power_in"))
      (node (ref "U3") (pin "11") (pinfunction "GND_2_11") (pintype "passive"))
      (node (ref "U3") (pin "31") (pinfunction "GND_31") (pintype "passive"))
    )
    (net (code "42") (name "GND_POWER") (class "Default")
      (node (ref "D4") (pin "A") (pinfunction "A_A") (pintype "passive"))
      (node (ref "M1") (pin "1") (pinfunction "G_1") (pintype "passive"))
      (node (ref "M1") (pin "3") (pinfunction "D_3") (pintype "passive"))
    )
    (net (code "43") (name "IO_A") (class "Default")
      (node (ref "JP13") (pin "6") (pinfunction "6_6") (pintype "passive"))
      (node (ref "JP15") (pin "5") (pinfunction "5_5") (pintype "passive"))
      (node (ref "U1") (pin "13") (pinfunction "IO0_13") (pintype "bidirectional"))
    )
    (net (code "44") (name "IO_B") (class "Default")
      (node (ref "JP13") (pin "5") (pinfunction "5_5") (pintype "passive"))
      (node (ref "JP15") (pin "4") (pinfunction "4_4") (pintype "passive"))
      (node (ref "U1") (pin "14") (pinfunction "IO1_14") (pintype "bidirectional"))
    )
    (net (code "45") (name "IO_C") (class "Default")
      (node (ref "JP13") (pin "4") (pinfunction "4_4") (pintype "passive"))
      (node (ref "JP15") (pin "3") (pinfunction "3_3") (pintype "passive"))
      (node (ref "U1") (pin "12") (pinfunction "IO3_12") (pintype "bidirectional"))
    )
    (net (code "46") (name "IO_D") (class "Default")
      (node (ref "JP13") (pin "3") (pinfunction "3_3") (pintype "passive"))
      (node (ref "JP15") (pin "2") (pinfunction "2_2") (pintype "passive"))
      (node (ref "U1") (pin "15") (pinfunction "IO2_15") (pintype "bidirectional"))
    )
    (net (code "47") (name "IO_DP") (class "Default")
      (node (ref "JP14") (pin "9") (pinfunction "9_9") (pintype "passive"))
      (node (ref "JP3") (pin "2") (pinfunction "2_2") (pintype "passive"))
      (node (ref "U1") (pin "1") (pinfunction "IO4_1") (pintype "bidirectional"))
    )
    (net (code "48") (name "IO_E") (class "Default")
      (node (ref "JP14") (pin "12") (pinfunction "12_12") (pintype "passive"))
      (node (ref "JP3") (pin "5") (pinfunction "5_5") (pintype "passive"))
      (node (ref "U1") (pin "2") (pinfunction "IO6_2") (pintype "bidirectional"))
    )
    (net (code "49") (name "IO_F") (class "Default")
      (node (ref "JP14") (pin "11") (pinfunction "11_11") (pintype "passive"))
      (node (ref "JP3") (pin "4") (pinfunction "4_4") (pintype "passive"))
      (node (ref "U1") (pin "4") (pinfunction "IO7_4") (pintype "bidirectional"))
    )
    (net (code "50") (name "IO_G") (class "Default")
      (node (ref "JP14") (pin "10") (pinfunction "10_10") (pintype "passive"))
      (node (ref "JP3") (pin "3") (pinfunction "3_3") (pintype "passive"))
      (node (ref "U1") (pin "5") (pinfunction "IO5_5") (pintype "bidirectional"))
    )
    (net (code "51") (name "Net-(C5-Pad1)") (class "Default")
      (node (ref "C5") (pin "1") (pinfunction "1_1") (pintype "passive"))
      (node (ref "R25") (pin "1") (pinfunction "1_1") (pintype "passive"))
      (node (ref "R3") (pin "2") (pinfunction "2_2") (pintype "passive"))
    )
    (net (code "52") (name "Net-(C11-1)") (class "Default")
      (node (ref "C11") (pin "3") (pinfunction "1_3") (pintype "passive"))
      (node (ref "U4") (pin "4") (pinfunction "BP_4") (pintype "input"))
    )
    (net (code "53") (name "Net-(C22-Pad1)") (class "Default")
      (node (ref "C22") (pin "1") (pinfunction "1_1") (pintype "passive"))
      (node (ref "R35") (pin "1") (pinfunction "1_1") (pintype "passive"))
      (node (ref "R48") (pin "2") (pinfunction "2_2") (pintype "passive"))
    )
    (net (code "54") (name "Net-(M2-D)") (class "Default")
      (node (ref "D12") (pin "A") (pinfunction "A_A") (pintype "passive"))
      (node (ref "M2") (pin "3") (pinfunction "D_3") (pintype "passive"))
    )
    (net (code "55") (name "Net-(M2-G)") (class "Default")
      (node (ref "44") (pin "1") (pinfunction "1_1") (pintype "passive"))
      (node (ref "M2") (pin "1") (pinfunction "G_1") (pintype "passive"))
      (node (ref "R28") (pin "2") (pinfunction "2_2") (pintype "passive"))
    )
    (net (code "56") (name "Net-(M3-G)") (class "Default")
      (node (ref "C22") (pin "2") (pinfunction "2_2") (pintype "passive"))
      (node (ref "M3") (pin "1") (pinfunction "G_1") (pintype "passive"))
      (node (ref "R34") (pin "1") (pinfunction "1_1") (pintype "passive"))
      (node (ref "R35") (pin "2") (pinfunction "2_2") (pintype "passive"))
    )
    (net (code "57") (name "Net-(M12-D)") (class "Default")
      (node (ref "D11") (pin "A") (pinfunction "A_A") (pintype "passive"))
      (node (ref "M12") (pin "3") (pinfunction "D_3") (pintype "passive"))
    )
    (net (code "58") (name "Net-(M12-G)") (class "Default")
      (node (ref "46") (pin "2") (pinfunction "2_2") (pintype "passive"))
      (node (ref "47") (pin "1") (pinfunction "1_1") (pintype "passive"))
      (node (ref "C6") (pin "1") (pinfunction "1_1") (pintype "passive"))
      (node (ref "M12") (pin "1") (pinfunction "G_1") (pintype "passive"))
    )
    (net (code "59") (name "Net-(R2-Pad2)") (class "Default")
      (node (ref "R2") (pin "2") (pinfunction "2_2") (pintype "passive"))
      (node (ref "R45") (pin "2") (pinfunction "2_2") (pintype "passive"))
      (node (ref "R5") (pin "2") (pinfunction "2_2") (pintype "passive"))
      (node (ref "U$1") (pin "IN+") (pinfunction "IN+_IN+") (pintype "bidirectional"))
    )
    (net (code "60") (name "Net-(R25-Pad2)") (class "Default")
      (node (ref "R25") (pin "2") (pinfunction "2_2") (pintype "passive"))
      (node (ref "S3") (pin "P$13") (pinfunction "3_P$13") (pintype "passive"))
      (node (ref "S3") (pin "P$14") (pinfunction "4_P$14") (pintype "passive"))
      (node (ref "S3") (pin "P$23") (pinfunction "3_P$23") (pintype "passive"))
      (node (ref "S3") (pin "P$24") (pinfunction "4_P$24") (pintype "passive"))
      (node (ref "S3") (pin "P$3") (pinfunction "3_P$3") (pintype "passive"))
      (node (ref "S3") (pin "P$4") (pinfunction "4_P$4") (pintype "passive"))
    )
    (net (code "61") (name "Net-(SG1-1)") (class "Default")
      (node (ref "C14") (pin "1") (pinfunction "1_1") (pintype "passive"))
      (node (ref "C9") (pin "1") (pinfunction "1_1") (pintype "passive"))
      (node (ref "R31") (pin "2") (pinfunction "2_2") (pintype "passive"))
      (node (ref "SG1") (pin "+") (pinfunction "1_+") (pintype "passive"))
    )
    (net (code "62") (name "Net-(SG1-2)") (class "Default")
      (node (ref "C15") (pin "1") (pinfunction "1_1") (pintype "passive"))
      (node (ref "C9") (pin "2") (pinfunction "2_2") (pintype "passive"))
      (node (ref "R32") (pin "1") (pinfunction "1_1") (pintype "passive"))
      (node (ref "SG1") (pin "-") (pinfunction "2_-") (pintype "passive"))
    )
    (net (code "63") (name "Net-(T1-PadE)") (class "Default")
      (node (ref "T1") (pin "E") (pinfunction "E_E") (pintype "passive"))
      (node (ref "T3") (pin "E") (pinfunction "E_E") (pintype "passive"))
    )
    (net (code "64") (name "P2") (class "Default")
      (node (ref "BH10") (pin "M1") (pinfunction "-_M1") (pintype "power_in"))
      (node (ref "BH10") (pin "M2") (pinfunction "-_M2") (pintype "power_in"))
      (node (ref "BH10") (pin "M3") (pinfunction "-_M3") (pintype "power_in"))
      (node (ref "BH10") (pin "M4") (pinfunction "-_M4") (pintype "power_in"))
      (node (ref "BH12") (pin "M1") (pinfunction "-_M1") (pintype "power_in"))
      (node (ref "BH12") (pin "M2") (pinfunction "-_M2") (pintype "power_in"))
      (node (ref "BH12") (pin "M3") (pinfunction "-_M3") (pintype "power_in"))
      (node (ref "BH12") (pin "M4") (pinfunction "-_M4") (pintype "power_in"))
    )
    (net (code "65") (name "P3") (class "Default")
      (node (ref "BH11") (pin "P1") (pinfunction "+_P1") (pintype "power_in"))
      (node (ref "BH11") (pin "P2") (pinfunction "+_P2") (pintype "power_in"))
      (node (ref "BH11") (pin "P3") (pinfunction "+_P3") (pintype "power_in"))
      (node (ref "BH11") (pin "P4") (pinfunction "+_P4") (pintype "power_in"))
      (node (ref "BH9") (pin "P1") (pinfunction "+_P1") (pintype "power_in"))
      (node (ref "BH9") (pin "P2") (pinfunction "+_P2") (pintype "power_in"))
      (node (ref "BH9") (pin "P3") (pinfunction "+_P3") (pintype "power_in"))
      (node (ref "BH9") (pin "P4") (pinfunction "+_P4") (pintype "power_in"))
    )
    (net (code "66") (name "R_") (class "Default")
      (node (ref "C18") (pin "1") (pinfunction "1_1") (pintype "passive"))
      (node (ref "R1") (pin "2") (pinfunction "2_2") (pintype "passive"))
      (node (ref "T1") (pin "B") (pinfunction "B_B") (pintype "passive"))
    )
    (net (code "67") (name "VCC") (class "Default")
      (node (ref "C1") (pin "1") (pinfunction "1_1") (pintype "passive"))
      (node (ref "C16") (pin "3") (pinfunction "1_3") (pintype "passive"))
      (node (ref "C17") (pin "1") (pinfunction "1_1") (pintype "passive"))
      (node (ref "C2") (pin "1") (pinfunction "1_1") (pintype "passive"))
      (node (ref "C3") (pin "1") (pinfunction "1_1") (pintype "passive"))
      (node (ref "D5") (pin "C") (pinfunction "C_C") (pintype "passive"))
      (node (ref "D7") (pin "A") (pinfunction "A_A") (pintype "passive"))
      (node (ref "D8") (pin "C") (pinfunction "C_C") (pintype "passive"))
      (node (ref "IC1") (pin "3") (pinfunction "VO_3") (pintype "passive"))
      (node (ref "JP1") (pin "5") (pinfunction "VCC_5") (pintype "passive"))
      (node (ref "M2") (pin "2") (pinfunction "S_2") (pintype "passive"))
      (node (ref "R1") (pin "1") (pinfunction "1_1") (pintype "passive"))
      (node (ref "R21") (pin "1") (pinfunction "1_1") (pintype "passive"))
      (node (ref "R22") (pin "1") (pinfunction "1_1") (pintype "passive"))
      (node (ref "R28") (pin "1") (pinfunction "1_1") (pintype "passive"))
      (node (ref "R4") (pin "1") (pinfunction "1_1") (pintype "passive"))
      (node (ref "R50") (pin "2") (pinfunction "2_2") (pintype "passive"))
      (node (ref "R7") (pin "2") (pinfunction "2_2") (pintype "passive"))
      (node (ref "T1") (pin "C") (pinfunction "C_C") (pintype "passive"))
      (node (ref "T2") (pin "E") (pinfunction "E_E") (pintype "passive"))
      (node (ref "U$3") (pin "VOUT") (pinfunction "VOUT_VOUT") (pintype "bidirectional"))
      (node (ref "U2") (pin "3") (pinfunction "VDD_3") (pintype "power_in"))
      (node (ref "U3") (pin "10") (pinfunction "VCC_10") (pintype "power_in"))
      (node (ref "U4") (pin "5") (pinfunction "OUT_5") (pintype "passive"))
    )
    (net (code "68") (name "VCC_IN") (class "Default")
      (node (ref "JP6") (pin "P3") (pinfunction "3_P3") (pintype "passive"))
      (node (ref "JP6") (pin "P3A") (pinfunction "3_P3A") (pintype "passive"))
      (node (ref "R20") (pin "2") (pinfunction "2_2") (pintype "passive"))
    )
    (net (code "69") (name "VIN_P") (class "Default")
      (node (ref "47") (pin "2") (pinfunction "2_2") (pintype "passive"))
      (node (ref "C6") (pin "2") (pinfunction "2_2") (pintype "passive"))
      (node (ref "D10") (pin "A") (pinfunction "A_A") (pintype "passive"))
      (node (ref "D9") (pin "A") (pinfunction "A_A") (pintype "passive"))
      (node (ref "R2") (pin "1") (pinfunction "1_1") (pintype "passive"))
      (node (ref "R45") (pin "1") (pinfunction "1_1") (pintype "passive"))
      (node (ref "R5") (pin "1") (pinfunction "1_1") (pintype "passive"))
    )
    (net (code "70") (name "V_IN") (class "Default")
      (node (ref "BH7") (pin "P1") (pinfunction "+_P1") (pintype "power_in"))
      (node (ref "BH7") (pin "P2") (pinfunction "+_P2") (pintype "power_in"))
      (node (ref "BH7") (pin "P3") (pinfunction "+_P3") (pintype "power_in"))
      (node (ref "BH7") (pin "P4") (pinfunction "+_P4") (pintype "power_in"))
      (node (ref "C13") (pin "2") (pinfunction "2_2") (pintype "passive"))
      (node (ref "C19") (pin "1") (pinfunction "1_1") (pintype "passive"))
      (node (ref "D3") (pin "C") (pinfunction "C_C") (pintype "passive"))
      (node (ref "D7") (pin "C") (pinfunction "C_C") (pintype "passive"))
      (node (ref "D9") (pin "C") (pinfunction "C_C") (pintype "passive"))
      (node (ref "IC1") (pin "2@1") (pinfunction "VI1_2@1") (pintype "input"))
      (node (ref "M3") (pin "2") (pinfunction "S_2") (pintype "passive"))
      (node (ref "R33") (pin "2") (pinfunction "2_2") (pintype "passive"))
      (node (ref "R34") (pin "2") (pinfunction "2_2") (pintype "passive"))
      (node (ref "S3") (pin "P$1") (pinfunction "1_P$1") (pintype "passive"))
      (node (ref "S3") (pin "P$11") (pinfunction "1_P$11") (pintype "passive"))
      (node (ref "S3") (pin "P$12") (pinfunction "2_P$12") (pintype "passive"))
      (node (ref "S3") (pin "P$15") (pinfunction "5_P$15") (pintype "passive"))
      (node (ref "S3") (pin "P$2") (pinfunction "2_P$2") (pintype "passive"))
      (node (ref "S3") (pin "P$21") (pinfunction "1_P$21") (pintype "passive"))
      (node (ref "S3") (pin "P$22") (pinfunction "2_P$22") (pintype "passive"))
      (node (ref "T2") (pin "B") (pinfunction "B_B") (pintype "passive"))
      (node (ref "T2") (pin "C") (pinfunction "C_C") (pintype "passive"))
      (node (ref "U$1") (pin "B+") (pinfunction "B+_B+") (pintype "bidirectional"))
      (node (ref "U$1") (pin "OUT+") (pinfunction "OUT+_OUT+") (pintype "bidirectional"))
      (node (ref "U$3") (pin "VIN") (pinfunction "VIN_VIN") (pintype "bidirectional"))
      (node (ref "U1") (pin "16") (pinfunction "VDD_16") (pintype "bidirectional"))
      (node (ref "U4") (pin "1") (pinfunction "IN_1") (pintype "input"))
    )
    (net (code "71") (name "XTAL1") (class "Default")
      (node (ref "C8") (pin "1") (pinfunction "1_1") (pintype "passive"))
      (node (ref "U3") (pin "13") (pinfunction "XTAL1_13") (pintype "input"))
      (node (ref "Y2") (pin "1") (pinfunction "1_1") (pintype "passive"))
    )
    (net (code "72") (name "XTAL2") (class "Default")
      (node (ref "C7") (pin "1") (pinfunction "1_1") (pintype "passive"))
      (node (ref "U3") (pin "12") (pinfunction "XTAL2_12") (pintype "output"))
      (node (ref "Y2") (pin "2") (pinfunction "2_2") (pintype "passive"))
    )
    (net (code "73") (name "XX_3") (class "Default")
      (node (ref "46") (pin "1") (pinfunction "1_1") (pintype "passive"))
      (node (ref "D10") (pin "C") (pinfunction "C_C") (pintype "passive"))
      (node (ref "D8") (pin "A") (pinfunction "A_A") (pintype "passive"))
      (node (ref "M12") (pin "2") (pinfunction "S_2") (pintype "passive"))
      (node (ref "R20") (pin "1") (pinfunction "1_1") (pintype "passive"))
    )
    (net (code "74") (name "unconnected-(IC1-VI-Pad2)") (class "Default")
      (node (ref "IC1") (pin "2") (pinfunction "VI_2") (pintype "input"))
    )
    (net (code "75") (name "{slash}RESET") (class "Default")
      (node (ref "JP1") (pin "P$1") (pinfunction "RST_P$1") (pintype "passive"))
      (node (ref "R6") (pin "1") (pinfunction "1_1") (pintype "passive"))
      (node (ref "T3") (pin "C") (pinfunction "C_C") (pintype "passive"))
      (node (ref "U3") (pin "9") (pinfunction "~{RESET}_9") (pintype "input"))
    )
  )
)
